# MotionMicrophone.net
KiCad netlist of a schematic drawn in Altium Designer
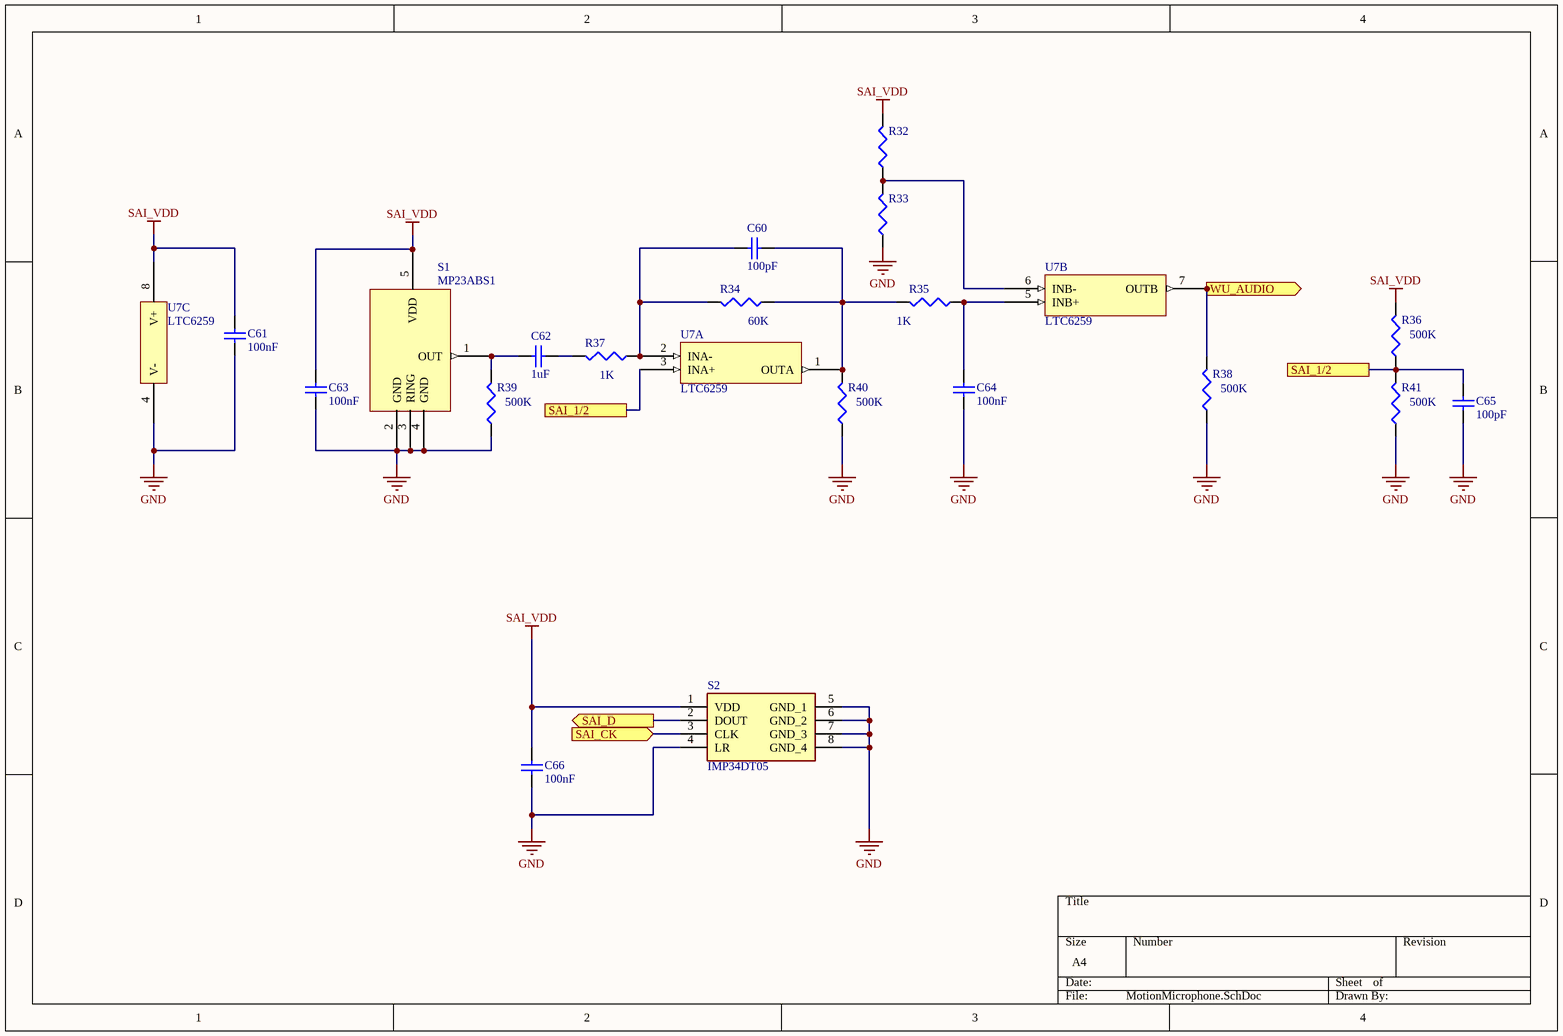
[diagram p0: MotionMicrophone.SchDoc]

(export (version "E")
  (design (tool "Eeschema 10.0.6"))
  (components
    (comp (ref "C60")
      (value "100pF")
      (footprint "CAPC1608X90X35NL10T15")
      (fields (field (name "PART NUMBER") "GRM188R71H102KA01D") (field (name "MANUFACTURER") "Murata"))
      (libsource (lib "Altium Content Vault") (part "CAP"))
    )
    (comp (ref "C61")
      (value "100nF")
      (footprint "CAPC1608X90X35NL10T15")
      (fields (field (name "PART NUMBER") "GRM188R71H102KA01D") (field (name "MANUFACTURER") "Murata"))
      (libsource (lib "Altium Content Vault") (part "CAP"))
    )
    (comp (ref "C62")
      (value "1uF")
      (footprint "CAPC1608X90X35NL10T15")
      (fields (field (name "PART NUMBER") "GRM188R71H102KA01D") (field (name "MANUFACTURER") "Murata"))
      (libsource (lib "Altium Content Vault") (part "CAP"))
    )
    (comp (ref "C63")
      (value "100nF")
      (footprint "CAPC1608X90X35NL10T15")
      (fields (field (name "PART NUMBER") "GRM188R71H102KA01D") (field (name "MANUFACTURER") "Murata"))
      (libsource (lib "Altium Content Vault") (part "CAP"))
    )
    (comp (ref "C64")
      (value "100nF")
      (footprint "CAPC1608X90X35NL10T15")
      (fields (field (name "PART NUMBER") "GRM188R71H102KA01D") (field (name "MANUFACTURER") "Murata"))
      (libsource (lib "Altium Content Vault") (part "CAP"))
    )
    (comp (ref "C65")
      (value "100pF")
      (footprint "CAPC1608X90X35NL10T15")
      (fields (field (name "PART NUMBER") "GRM188R71H102KA01D") (field (name "MANUFACTURER") "Murata"))
      (libsource (lib "Altium Content Vault") (part "CAP"))
    )
    (comp (ref "C66")
      (value "100nF")
      (footprint "CAPC1608X90X35NL10T15")
      (fields (field (name "PART NUMBER") "GRM188R71H102KA01D") (field (name "MANUFACTURER") "Murata"))
      (libsource (lib "Altium Content Vault") (part "CAP"))
    )
    (comp (ref "R32")
      (value "~")
      (footprint "J1-0603")
      (description "Resistor")
      (fields (field (name "PUBLISHER") "Altium Limited"))
      (libsource (lib "Miscellaneous Devices") (part "Res3"))
    )
    (comp (ref "R33")
      (value "~")
      (footprint "J1-0603")
      (description "Resistor")
      (fields (field (name "PUBLISHER") "Altium Limited"))
      (libsource (lib "Miscellaneous Devices") (part "Res3"))
    )
    (comp (ref "R34")
      (value "60K")
      (footprint "J1-0603")
      (description "Resistor")
      (fields (field (name "PUBLISHER") "Altium Limited"))
      (libsource (lib "Miscellaneous Devices") (part "Res3"))
    )
    (comp (ref "R35")
      (value "1K")
      (footprint "J1-0603")
      (description "Resistor")
      (fields (field (name "PUBLISHER") "Altium Limited"))
      (libsource (lib "Miscellaneous Devices") (part "Res3"))
    )
    (comp (ref "R36")
      (value "500K")
      (footprint "J1-0603")
      (description "Resistor")
      (fields (field (name "PUBLISHER") "Altium Limited"))
      (libsource (lib "Miscellaneous Devices") (part "Res3"))
    )
    (comp (ref "R37")
      (value "1K")
      (footprint "J1-0603")
      (description "Resistor")
      (fields (field (name "PUBLISHER") "Altium Limited"))
      (libsource (lib "Miscellaneous Devices") (part "Res3"))
    )
    (comp (ref "R38")
      (value "500K")
      (footprint "J1-0603")
      (description "Resistor")
      (fields (field (name "PUBLISHER") "Altium Limited"))
      (libsource (lib "Miscellaneous Devices") (part "Res3"))
    )
    (comp (ref "R39")
      (value "500K")
      (footprint "J1-0603")
      (description "Resistor")
      (fields (field (name "PUBLISHER") "Altium Limited"))
      (libsource (lib "Miscellaneous Devices") (part "Res3"))
    )
    (comp (ref "R40")
      (value "500K")
      (footprint "J1-0603")
      (description "Resistor")
      (fields (field (name "PUBLISHER") "Altium Limited"))
      (libsource (lib "Miscellaneous Devices") (part "Res3"))
    )
    (comp (ref "R41")
      (value "500K")
      (footprint "J1-0603")
      (description "Resistor")
      (fields (field (name "PUBLISHER") "Altium Limited"))
      (libsource (lib "Miscellaneous Devices") (part "Res3"))
    )
    (comp (ref "S1")
      (value "MP23ABS1")
      (footprint "MP23ABS1")
      (libsource (lib "STM32WB55RGV7") (part "MP23ABS1"))
    )
    (comp (ref "S2")
      (value "IMP34DT05")
      (footprint "SamacSys:IMP34DT05")
      (description "Integrated Circuit")
      (libsource (lib "*") (part "IMP34DT05"))
    )
    (comp (ref "U7")
      (value "LTC6259")
      (footprint "SOT23-8")
      (libsource (lib "STM32WB55RGV7") (part "LTC6259"))
    )
  )
  (nets
    (net (code "1") (name "/SAI_1{slash}2") (class "Default")
      (node (ref "C65") (pin "1") (pinfunction "1_1") (pintype "passive"))
      (node (ref "R36") (pin "1") (pinfunction "1_1") (pintype "passive"))
      (node (ref "R41") (pin "2") (pinfunction "2_2") (pintype "passive"))
      (node (ref "U7") (pin "3") (pinfunction "INA+_3") (pintype "input"))
    )
    (net (code "2") (name "/SAI_CK") (class "Default")
      (node (ref "S2") (pin "3") (pinfunction "CLK_3") (pintype "passive"))
    )
    (net (code "3") (name "/SAI_D") (class "Default")
      (node (ref "S2") (pin "2") (pinfunction "DOUT_2") (pintype "passive"))
    )
    (net (code "4") (name "/WU_AUDIO") (class "Default")
      (node (ref "R38") (pin "2") (pinfunction "2_2") (pintype "passive"))
      (node (ref "U7") (pin "7") (pinfunction "OUTB_7") (pintype "output"))
    )
    (net (code "5") (name "GND") (class "Default")
      (node (ref "C61") (pin "1") (pinfunction "1_1") (pintype "passive"))
      (node (ref "C63") (pin "1") (pinfunction "1_1") (pintype "passive"))
      (node (ref "C64") (pin "1") (pinfunction "1_1") (pintype "passive"))
      (node (ref "C65") (pin "2") (pinfunction "2_2") (pintype "passive"))
      (node (ref "C66") (pin "1") (pinfunction "1_1") (pintype "passive"))
      (node (ref "R33") (pin "1") (pinfunction "1_1") (pintype "passive"))
      (node (ref "R38") (pin "1") (pinfunction "1_1") (pintype "passive"))
      (node (ref "R39") (pin "1") (pinfunction "1_1") (pintype "passive"))
      (node (ref "R40") (pin "1") (pinfunction "1_1") (pintype "passive"))
      (node (ref "R41") (pin "1") (pinfunction "1_1") (pintype "passive"))
      (node (ref "S1") (pin "2") (pinfunction "GND_2") (pintype "power_in"))
      (node (ref "S1") (pin "3") (pinfunction "RING_3") (pintype "power_in"))
      (node (ref "S1") (pin "4") (pinfunction "GND_4") (pintype "power_in"))
      (node (ref "S2") (pin "4") (pinfunction "LR_4") (pintype "passive"))
      (node (ref "S2") (pin "5") (pinfunction "GND_1_5") (pintype "passive"))
      (node (ref "S2") (pin "6") (pinfunction "GND_2_6") (pintype "passive"))
      (node (ref "S2") (pin "7") (pinfunction "GND_3_7") (pintype "passive"))
      (node (ref "S2") (pin "8") (pinfunction "GND_4_8") (pintype "passive"))
      (node (ref "U7") (pin "4") (pinfunction "V-_4") (pintype "power_in"))
    )
    (net (code "6") (name "Net-(C62-Pad1)") (class "Default")
      (node (ref "C62") (pin "1") (pinfunction "1_1") (pintype "passive"))
      (node (ref "R37") (pin "2") (pinfunction "2_2") (pintype "passive"))
    )
    (net (code "7") (name "Net-(S1-OUT)") (class "Default")
      (node (ref "C62") (pin "2") (pinfunction "2_2") (pintype "passive"))
      (node (ref "R39") (pin "2") (pinfunction "2_2") (pintype "passive"))
      (node (ref "S1") (pin "1") (pinfunction "OUT_1") (pintype "output"))
    )
    (net (code "8") (name "Net-(U7A-INA-)") (class "Default")
      (node (ref "C60") (pin "2") (pinfunction "2_2") (pintype "passive"))
      (node (ref "R34") (pin "2") (pinfunction "2_2") (pintype "passive"))
      (node (ref "R37") (pin "1") (pinfunction "1_1") (pintype "passive"))
      (node (ref "U7") (pin "2") (pinfunction "INA-_2") (pintype "input"))
    )
    (net (code "9") (name "Net-(U7A-OUTA)") (class "Default")
      (node (ref "C60") (pin "1") (pinfunction "1_1") (pintype "passive"))
      (node (ref "R34") (pin "1") (pinfunction "1_1") (pintype "passive"))
      (node (ref "R35") (pin "2") (pinfunction "2_2") (pintype "passive"))
      (node (ref "R40") (pin "2") (pinfunction "2_2") (pintype "passive"))
      (node (ref "U7") (pin "1") (pinfunction "OUTA_1") (pintype "output"))
    )
    (net (code "10") (name "Net-(U7B-INB+)") (class "Default")
      (node (ref "C64") (pin "2") (pinfunction "2_2") (pintype "passive"))
      (node (ref "R35") (pin "1") (pinfunction "1_1") (pintype "passive"))
      (node (ref "U7") (pin "5") (pinfunction "INB+_5") (pintype "input"))
    )
    (net (code "11") (name "Net-(U7B-INB-)") (class "Default")
      (node (ref "R32") (pin "1") (pinfunction "1_1") (pintype "passive"))
      (node (ref "R33") (pin "2") (pinfunction "2_2") (pintype "passive"))
      (node (ref "U7") (pin "6") (pinfunction "INB-_6") (pintype "input"))
    )
    (net (code "12") (name "SAI_VDD") (class "Default")
      (node (ref "C61") (pin "2") (pinfunction "2_2") (pintype "passive"))
      (node (ref "C63") (pin "2") (pinfunction "2_2") (pintype "passive"))
      (node (ref "C66") (pin "2") (pinfunction "2_2") (pintype "passive"))
      (node (ref "R32") (pin "2") (pinfunction "2_2") (pintype "passive"))
      (node (ref "R36") (pin "2") (pinfunction "2_2") (pintype "passive"))
      (node (ref "S1") (pin "5") (pinfunction "VDD_5") (pintype "power_in"))
      (node (ref "S2") (pin "1") (pinfunction "VDD_1") (pintype "passive"))
      (node (ref "U7") (pin "8") (pinfunction "V+_8") (pintype "power_in"))
    )
  )
)
